# BEEP.net
KiCad netlist of a schematic drawn in Altium Designer
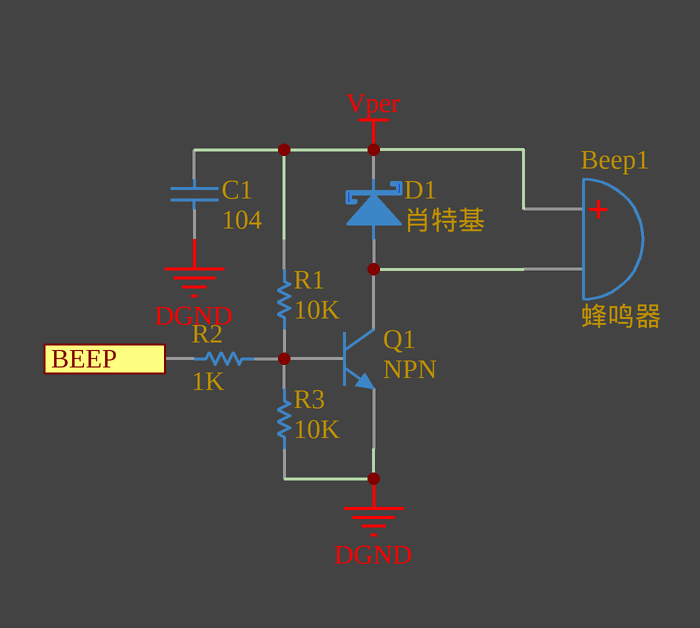
[diagram p0: BEEP.SchDoc]

(export (version "E")
  (design (tool "Eeschema 10.0.6"))
  (components
    (comp (ref "Beep1") (value "蜂鸣器") (footprint "Beep-5.0*5.0") (libsource (lib "iMag") (part "蜂鸣器")))
    (comp (ref "C1")
      (value "104")
      (footprint "C0402")
      (description "Capacitor")
      (fields (field (name "PUBLISHER") "Altium Limited"))
      (libsource (lib "iMag") (part "电容"))
    )
    (comp (ref "D1")
      (value "肖特基")
      (footprint "SOD-123F")
      (description "Schottky Diode")
      (libsource (lib "iMag") (part "肖特基"))
    )
    (comp (ref "Q1")
      (value "NPN")
      (footprint "SOT-23")
      (description "NPN Bipolar Transistor")
      (fields (field (name "PUBLISHER") "Altium Limited"))
      (libsource (lib "iMag") (part "NPN"))
    )
    (comp (ref "R1")
      (value "10K")
      (footprint "R0402")
      (description "Resistor")
      (fields (field (name "PUBLISHER") "Altium Limited"))
      (libsource (lib "iMag") (part "电阻"))
    )
    (comp (ref "R2")
      (value "1K")
      (footprint "R0402")
      (description "Resistor")
      (fields (field (name "PUBLISHER") "Altium Limited"))
      (libsource (lib "iMag") (part "电阻"))
    )
    (comp (ref "R3")
      (value "10K")
      (footprint "R0402")
      (description "Resistor")
      (fields (field (name "PUBLISHER") "Altium Limited"))
      (libsource (lib "iMag") (part "电阻"))
    )
  )
  (nets
    (net (code "1") (name "/BEEP") (class "Default")
      (node (ref "R2") (pin "2") (pinfunction "2_2") (pintype "passive"))
    )
    (net (code "2") (name "DGND") (class "Default")
      (node (ref "C1") (pin "1") (pinfunction "1_1") (pintype "passive"))
      (node (ref "Q1") (pin "2") (pinfunction "E_2") (pintype "passive"))
      (node (ref "R3") (pin "1") (pinfunction "1_1") (pintype "passive"))
    )
    (net (code "3") (name "Net-(Beep1-B)") (class "Default")
      (node (ref "Beep1") (pin "2") (pinfunction "B_2") (pintype "passive"))
      (node (ref "D1") (pin "1") (pinfunction "A_1") (pintype "passive"))
      (node (ref "Q1") (pin "3") (pinfunction "C_3") (pintype "passive"))
    )
    (net (code "4") (name "Net-(Q1-B)") (class "Default")
      (node (ref "Q1") (pin "1") (pinfunction "B_1") (pintype "passive"))
      (node (ref "R1") (pin "1") (pinfunction "1_1") (pintype "passive"))
      (node (ref "R2") (pin "1") (pinfunction "1_1") (pintype "passive"))
      (node (ref "R3") (pin "2") (pinfunction "2_2") (pintype "passive"))
    )
    (net (code "5") (name "Vper") (class "Default")
      (node (ref "Beep1") (pin "1") (pinfunction "A_1") (pintype "passive"))
      (node (ref "C1") (pin "2") (pinfunction "2_2") (pintype "passive"))
      (node (ref "D1") (pin "2") (pinfunction "K_2") (pintype "passive"))
      (node (ref "R1") (pin "2") (pinfunction "2_2") (pintype "passive"))
    )
  )
)
